# Nusbio_Test_GPIOS_Extension.net
KiCad netlist of a schematic drawn in EAGLE
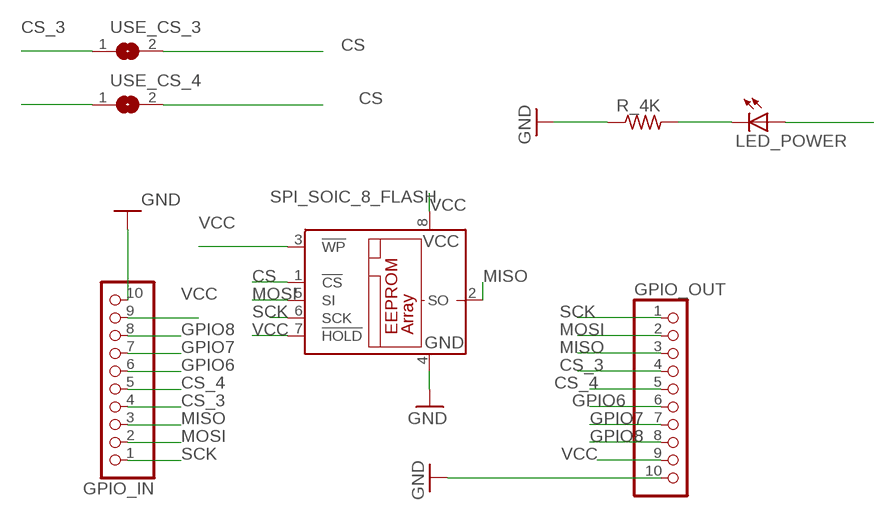
[diagram p0: schematic, sheet 1]

(export (version "E")
  (design (tool "Eeschema 10.0.6"))
  (components
    (comp (ref "GPIO_IN")
      (value "PINHD-1X10")
      (footprint "eagle-import:1X10-BIG")
      (libsource (lib "eagle-import") (part "PINHD-1X10"))
    )
    (comp (ref "GPIO_OUT")
      (value "PINHD-1X10")
      (footprint "eagle-import:1X10-BIG")
      (libsource (lib "eagle-import") (part "PINHD-1X10"))
    )
    (comp (ref "LED_POWER")
      (value "LEDSMT1206")
      (footprint "eagle-import:1206")
      (libsource (lib "eagle-import") (part "LEDSMT1206"))
    )
    (comp (ref "R_4K")
      (value "R-US_R1206")
      (footprint "eagle-import:R1206")
      (libsource (lib "eagle-import") (part "R-US_R1206"))
    )
    (comp (ref "SPI_SOIC_8_FLASH")
      (value "25AA080SN")
      (footprint "eagle-import:SO-08")
      (fields (field (name "MF") "MICROCHIP") (field (name "MPN") "25AA080/SN"))
      (libsource (lib "eagle-import") (part "25SNAA080"))
    )
    (comp (ref "USE_CS_3")
      (value "SOLDERJUMPERREFLOW")
      (footprint "eagle-import:SOLDERJUMPER_REFLOW")
      (libsource (lib "eagle-import") (part "SOLDERJUMPERREFLOW"))
    )
    (comp (ref "USE_CS_4")
      (value "SOLDERJUMPERREFLOW")
      (footprint "eagle-import:SOLDERJUMPER_REFLOW")
      (libsource (lib "eagle-import") (part "SOLDERJUMPERREFLOW"))
    )
  )
  (nets
    (net (code "1") (name "/CS") (class "Default")
      (node (ref "SPI_SOIC_8_FLASH") (pin "1") (pinfunction "~{CS}_1") (pintype "input"))
      (node (ref "USE_CS_3") (pin "2") (pinfunction "2_2") (pintype "passive"))
      (node (ref "USE_CS_4") (pin "2") (pinfunction "2_2") (pintype "passive"))
    )
    (net (code "2") (name "/CS_3") (class "Default")
      (node (ref "GPIO_IN") (pin "4") (pinfunction "4_4") (pintype "passive"))
      (node (ref "GPIO_OUT") (pin "4") (pinfunction "4_4") (pintype "passive"))
      (node (ref "USE_CS_3") (pin "1") (pinfunction "1_1") (pintype "passive"))
    )
    (net (code "3") (name "/CS_4") (class "Default")
      (node (ref "GPIO_IN") (pin "5") (pinfunction "5_5") (pintype "passive"))
      (node (ref "GPIO_OUT") (pin "5") (pinfunction "5_5") (pintype "passive"))
      (node (ref "USE_CS_4") (pin "1") (pinfunction "1_1") (pintype "passive"))
    )
    (net (code "4") (name "/GPIO6") (class "Default")
      (node (ref "GPIO_IN") (pin "6") (pinfunction "6_6") (pintype "passive"))
      (node (ref "GPIO_OUT") (pin "6") (pinfunction "6_6") (pintype "passive"))
    )
    (net (code "5") (name "/GPIO7") (class "Default")
      (node (ref "GPIO_IN") (pin "7") (pinfunction "7_7") (pintype "passive"))
      (node (ref "GPIO_OUT") (pin "7") (pinfunction "7_7") (pintype "passive"))
    )
    (net (code "6") (name "/GPIO8") (class "Default")
      (node (ref "GPIO_IN") (pin "8") (pinfunction "8_8") (pintype "passive"))
      (node (ref "GPIO_OUT") (pin "8") (pinfunction "8_8") (pintype "passive"))
    )
    (net (code "7") (name "/MISO") (class "Default")
      (node (ref "GPIO_IN") (pin "3") (pinfunction "3_3") (pintype "passive"))
      (node (ref "GPIO_OUT") (pin "3") (pinfunction "3_3") (pintype "passive"))
      (node (ref "SPI_SOIC_8_FLASH") (pin "2") (pinfunction "SO_2") (pintype "bidirectional"))
    )
    (net (code "8") (name "/MOSI") (class "Default")
      (node (ref "GPIO_IN") (pin "2") (pinfunction "2_2") (pintype "passive"))
      (node (ref "GPIO_OUT") (pin "2") (pinfunction "2_2") (pintype "passive"))
      (node (ref "SPI_SOIC_8_FLASH") (pin "5") (pinfunction "SI_5") (pintype "input"))
    )
    (net (code "9") (name "/SCK") (class "Default")
      (node (ref "GPIO_IN") (pin "1") (pinfunction "1_1") (pintype "passive"))
      (node (ref "GPIO_OUT") (pin "1") (pinfunction "1_1") (pintype "passive"))
      (node (ref "SPI_SOIC_8_FLASH") (pin "6") (pinfunction "SCK_6") (pintype "input"))
    )
    (net (code "10") (name "/VCC") (class "Default")
      (node (ref "GPIO_IN") (pin "9") (pinfunction "9_9") (pintype "passive"))
      (node (ref "GPIO_OUT") (pin "9") (pinfunction "9_9") (pintype "passive"))
      (node (ref "LED_POWER") (pin "A") (pinfunction "A_A") (pintype "passive"))
      (node (ref "SPI_SOIC_8_FLASH") (pin "3") (pinfunction "~{WP}_3") (pintype "input"))
      (node (ref "SPI_SOIC_8_FLASH") (pin "7") (pinfunction "~{HOLD}_7") (pintype "input"))
      (node (ref "SPI_SOIC_8_FLASH") (pin "8") (pinfunction "VCC_8") (pintype "power_in"))
    )
    (net (code "11") (name "GND") (class "Default")
      (node (ref "GPIO_IN") (pin "10") (pinfunction "10_10") (pintype "passive"))
      (node (ref "GPIO_OUT") (pin "10") (pinfunction "10_10") (pintype "passive"))
      (node (ref "R_4K") (pin "1") (pinfunction "1_1") (pintype "passive"))
      (node (ref "SPI_SOIC_8_FLASH") (pin "4") (pinfunction "GND_4") (pintype "power_in"))
    )
    (net (code "12") (name "Net-(LED_POWER-PadC)") (class "Default")
      (node (ref "LED_POWER") (pin "C") (pinfunction "C_C") (pintype "passive"))
      (node (ref "R_4K") (pin "2") (pinfunction "2_2") (pintype "passive"))
    )
  )
)
